# Top_Level.net
KiCad netlist of a schematic drawn in Altium Designer
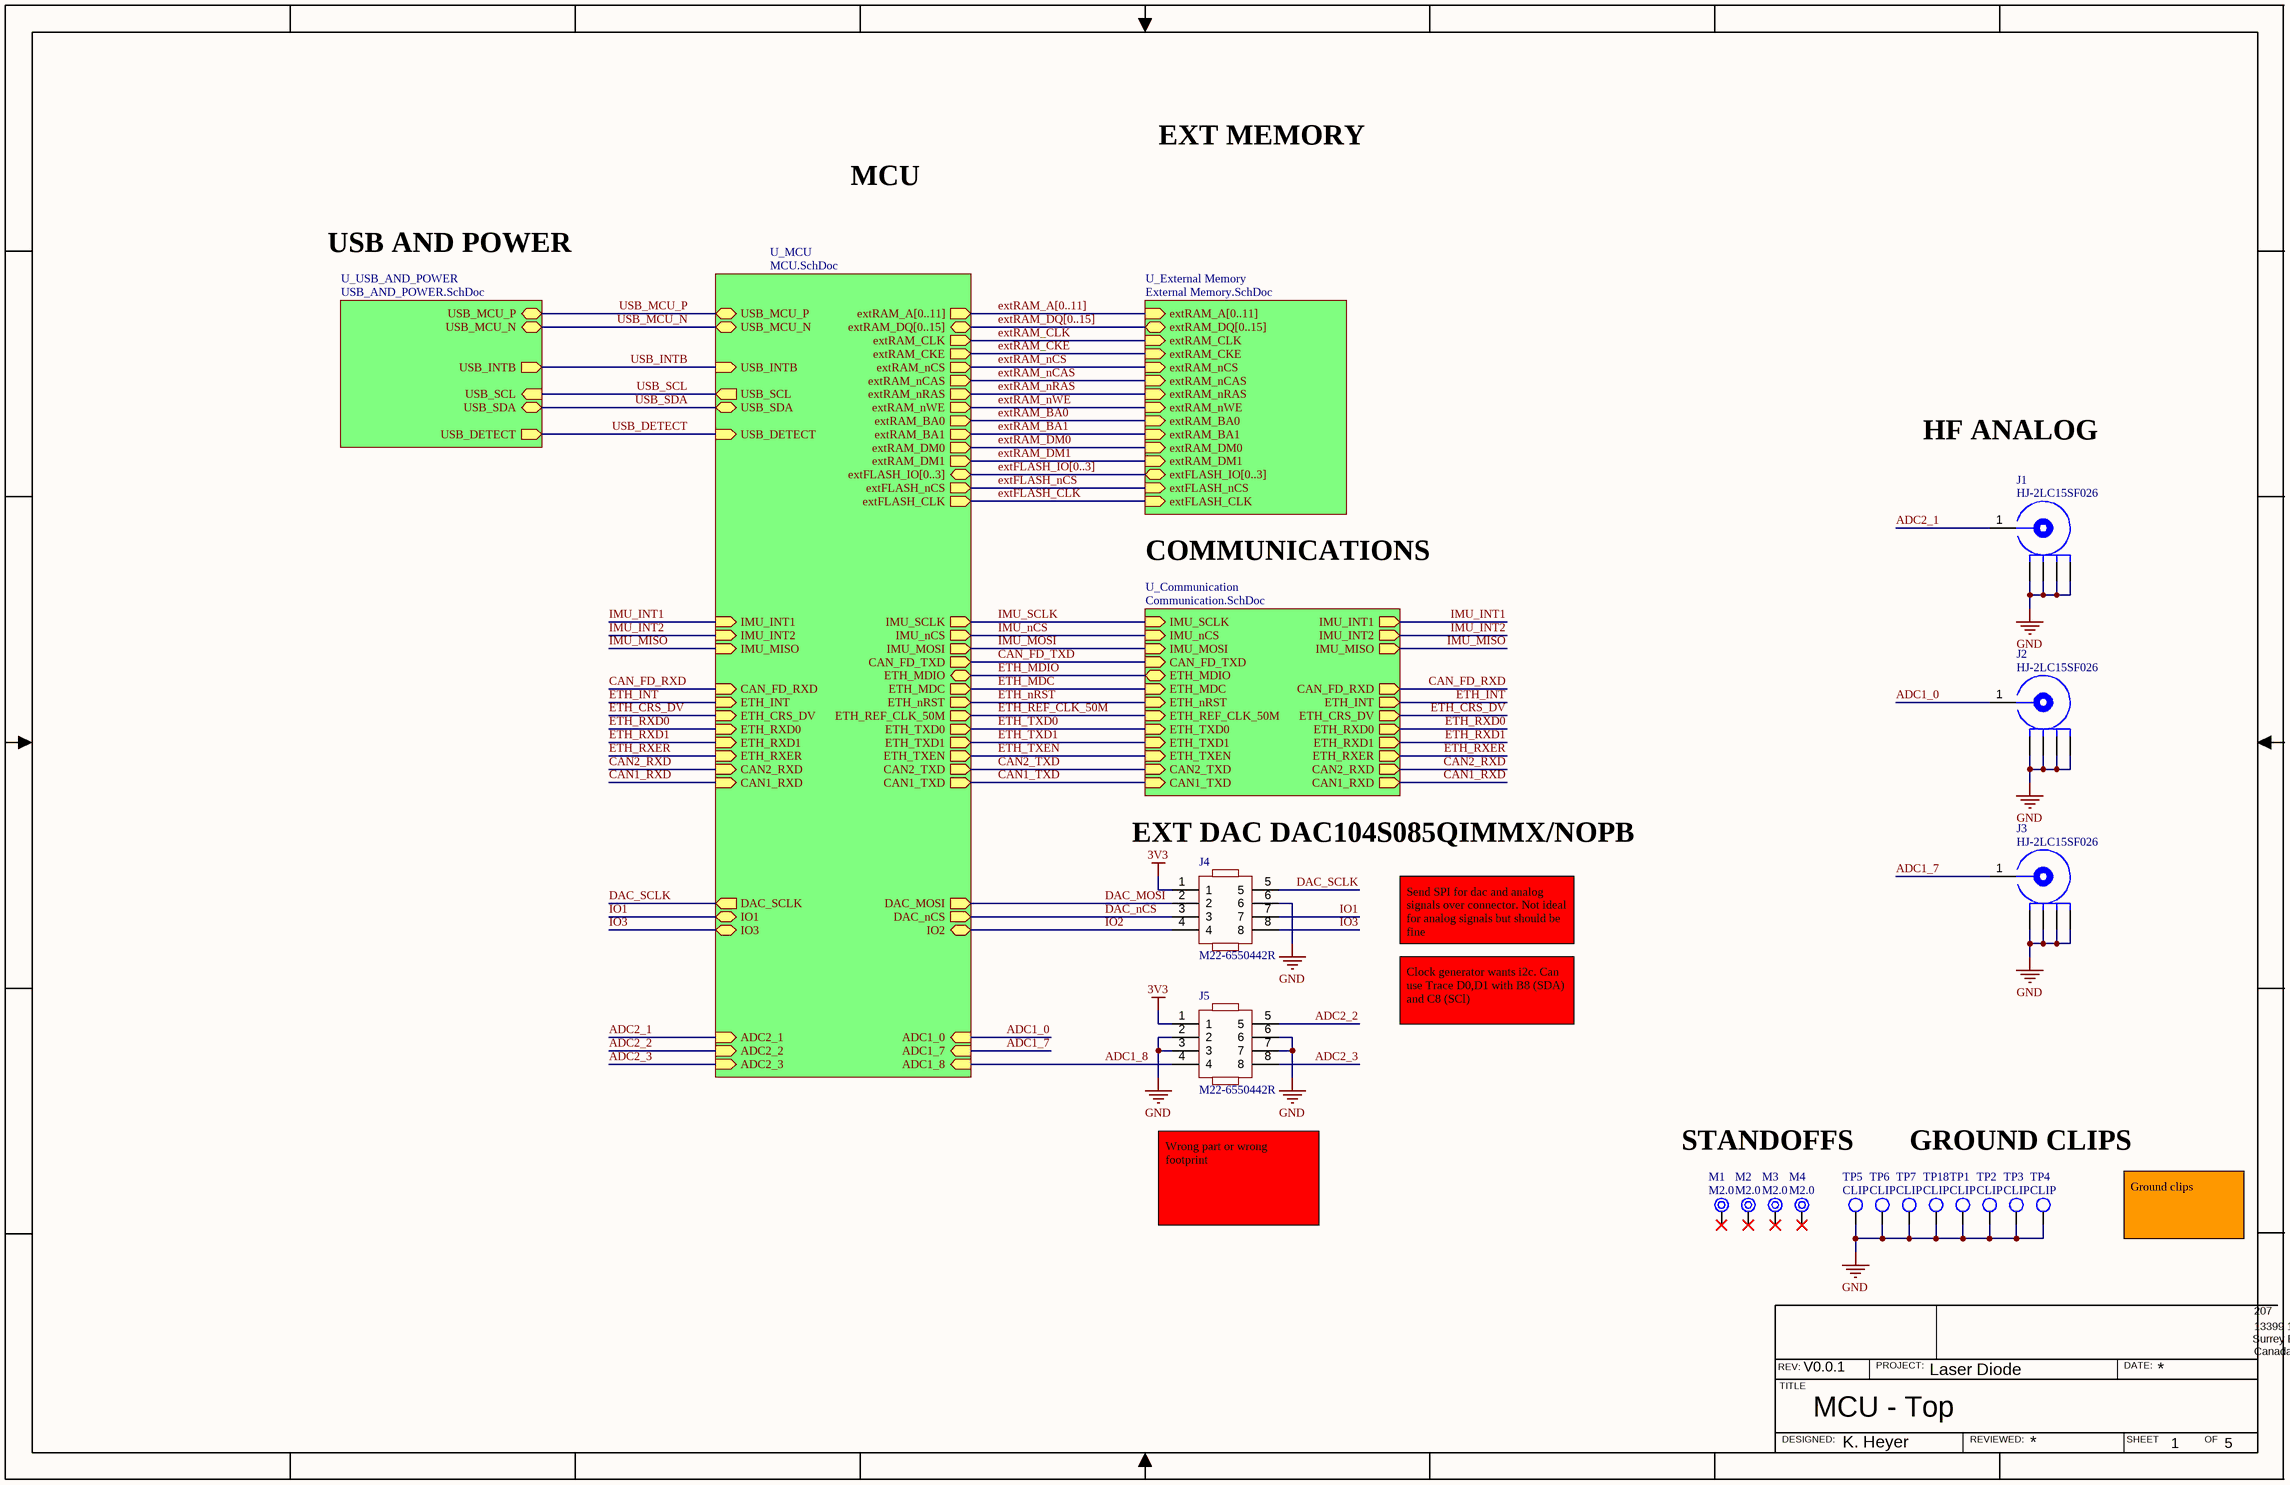
[diagram p0: Top_Level.SchDoc]

(export (version "E")
  (design (tool "Eeschema 10.0.6"))
  (components
    (comp (ref "J1")
      (value "HJ-2LC15SF026")
      (footprint "SMA TH RA BORE")
      (libsource (lib "MCU") (part "CON SMA BORE SMD RA HJ-2LC15SF026"))
    )
    (comp (ref "J2")
      (value "HJ-2LC15SF026")
      (footprint "SMA TH RA BORE")
      (libsource (lib "MCU") (part "CON SMA BORE SMD RA HJ-2LC15SF026"))
    )
    (comp (ref "J3")
      (value "HJ-2LC15SF026")
      (footprint "SMA TH RA BORE")
      (libsource (lib "MCU") (part "CON SMA BORE SMD RA HJ-2LC15SF026"))
    )
    (comp (ref "J4")
      (value "M22-6550442R")
      (footprint "CONN HDR 08 FEMALE RA 2ROW")
      (description "Conn Socket Strip RCP 8 POS 2mm Solder RA SMD T/R")
      (fields (field (name "MANUFACTURER") "Harwin"))
      (libsource (lib "OPAMP_DEV_SOT5_6-23") (part "CONN HDR 08 FEMALE RA 2 ROW"))
    )
    (comp (ref "J5")
      (value "M22-6550442R")
      (footprint "CONN HDR 08 FEMALE RA 2ROW")
      (description "Conn Socket Strip RCP 8 POS 2mm Solder RA SMD T/R")
      (fields (field (name "MANUFACTURER") "Harwin"))
      (libsource (lib "OPAMP_DEV_SOT5_6-23") (part "CONN HDR 08 FEMALE RA 2 ROW"))
    )
    (comp (ref "M1")
      (value "M2.0")
      (footprint "MECH M2.0 UNPLATED")
      (libsource (lib "OPAMP_DEV_SOT5_6-23") (part "MECH M2.0 UNPLATED"))
    )
    (comp (ref "M2")
      (value "M2.0")
      (footprint "MECH M2.0 UNPLATED")
      (libsource (lib "OPAMP_DEV_SOT5_6-23") (part "MECH M2.0 UNPLATED"))
    )
    (comp (ref "M3")
      (value "M2.0")
      (footprint "MECH M2.0 UNPLATED")
      (libsource (lib "OPAMP_DEV_SOT5_6-23") (part "MECH M2.0 UNPLATED"))
    )
    (comp (ref "M4")
      (value "M2.0")
      (footprint "MECH M2.0 UNPLATED")
      (libsource (lib "OPAMP_DEV_SOT5_6-23") (part "MECH M2.0 UNPLATED"))
    )
    (comp (ref "TP1")
      (value "CLIP")
      (footprint "TESTPOINT_CLIP_1206")
      (description "Current Sense Resistors - SMD CHIP CHECKER HT=2.0 1206")
      (fields (field (name "MANUFACTURER") "KOA Speer") (field (name "MANUFACTURER PART NUMBER") "RCWCTE"))
      (libsource (lib "DClassAmp_Symbol") (part "TP CLIP 1206 RCWCTE"))
    )
    (comp (ref "TP2")
      (value "CLIP")
      (footprint "TESTPOINT_CLIP_1206")
      (description "Current Sense Resistors - SMD CHIP CHECKER HT=2.0 1206")
      (fields (field (name "MANUFACTURER") "KOA Speer") (field (name "MANUFACTURER PART NUMBER") "RCWCTE"))
      (libsource (lib "DClassAmp_Symbol") (part "TP CLIP 1206 RCWCTE"))
    )
    (comp (ref "TP3")
      (value "CLIP")
      (footprint "TESTPOINT_CLIP_1206")
      (description "Current Sense Resistors - SMD CHIP CHECKER HT=2.0 1206")
      (fields (field (name "MANUFACTURER") "KOA Speer") (field (name "MANUFACTURER PART NUMBER") "RCWCTE"))
      (libsource (lib "DClassAmp_Symbol") (part "TP CLIP 1206 RCWCTE"))
    )
    (comp (ref "TP4")
      (value "CLIP")
      (footprint "TESTPOINT_CLIP_1206")
      (description "Current Sense Resistors - SMD CHIP CHECKER HT=2.0 1206")
      (fields (field (name "MANUFACTURER") "KOA Speer") (field (name "MANUFACTURER PART NUMBER") "RCWCTE"))
      (libsource (lib "DClassAmp_Symbol") (part "TP CLIP 1206 RCWCTE"))
    )
    (comp (ref "TP5")
      (value "CLIP")
      (footprint "TESTPOINT_CLIP_1206")
      (description "Current Sense Resistors - SMD CHIP CHECKER HT=2.0 1206")
      (fields (field (name "MANUFACTURER") "KOA Speer") (field (name "MANUFACTURER PART NUMBER") "RCWCTE"))
      (libsource (lib "DClassAmp_Symbol") (part "TP CLIP 1206 RCWCTE"))
    )
    (comp (ref "TP6")
      (value "CLIP")
      (footprint "TESTPOINT_CLIP_1206")
      (description "Current Sense Resistors - SMD CHIP CHECKER HT=2.0 1206")
      (fields (field (name "MANUFACTURER") "KOA Speer") (field (name "MANUFACTURER PART NUMBER") "RCWCTE"))
      (libsource (lib "DClassAmp_Symbol") (part "TP CLIP 1206 RCWCTE"))
    )
    (comp (ref "TP7")
      (value "CLIP")
      (footprint "TESTPOINT_CLIP_1206")
      (description "Current Sense Resistors - SMD CHIP CHECKER HT=2.0 1206")
      (fields (field (name "MANUFACTURER") "KOA Speer") (field (name "MANUFACTURER PART NUMBER") "RCWCTE"))
      (libsource (lib "DClassAmp_Symbol") (part "TP CLIP 1206 RCWCTE"))
    )
    (comp (ref "TP18")
      (value "CLIP")
      (footprint "TESTPOINT_CLIP_1206")
      (description "Current Sense Resistors - SMD CHIP CHECKER HT=2.0 1206")
      (fields (field (name "MANUFACTURER") "KOA Speer") (field (name "MANUFACTURER PART NUMBER") "RCWCTE"))
      (libsource (lib "DClassAmp_Symbol") (part "TP CLIP 1206 RCWCTE"))
    )
  )
  (nets
    (net (code "33") (name "/ADC1_0") (class "Default")
      (node (ref "J2") (pin "1") (pinfunction "1_1") (pintype "passive"))
    )
    (net (code "34") (name "/ADC1_7") (class "Default")
      (node (ref "J3") (pin "1") (pinfunction "1_1") (pintype "passive"))
    )
    (net (code "35") (name "/ADC1_8") (class "Default")
      (node (ref "J5") (pin "4") (pinfunction "4_4") (pintype "passive"))
    )
    (net (code "36") (name "/ADC2_1") (class "Default")
      (node (ref "J1") (pin "1") (pinfunction "1_1") (pintype "passive"))
    )
    (net (code "37") (name "/ADC2_2") (class "Default")
      (node (ref "J5") (pin "5") (pinfunction "5_5") (pintype "passive"))
    )
    (net (code "38") (name "/ADC2_3") (class "Default")
      (node (ref "J5") (pin "8") (pinfunction "8_8") (pintype "passive"))
    )
    (net (code "45") (name "/DAC_MOSI") (class "Default")
      (node (ref "J4") (pin "2") (pinfunction "2_2") (pintype "passive"))
    )
    (net (code "46") (name "/DAC_SCLK") (class "Default")
      (node (ref "J4") (pin "5") (pinfunction "5_5") (pintype "passive"))
    )
    (net (code "47") (name "/DAC_nCS") (class "Default")
      (node (ref "J4") (pin "3") (pinfunction "3_3") (pintype "passive"))
    )
    (net (code "66") (name "/IO1") (class "Default")
      (node (ref "J4") (pin "7") (pinfunction "7_7") (pintype "passive"))
    )
    (net (code "67") (name "/IO2") (class "Default")
      (node (ref "J4") (pin "4") (pinfunction "4_4") (pintype "passive"))
    )
    (net (code "68") (name "/IO3") (class "Default")
      (node (ref "J4") (pin "8") (pinfunction "8_8") (pintype "passive"))
    )
    (net (code "90") (name "3V3") (class "Default")
      (node (ref "J4") (pin "1") (pinfunction "1_1") (pintype "passive"))
      (node (ref "J5") (pin "1") (pinfunction "1_1") (pintype "passive"))
    )
    (net (code "91") (name "GND") (class "Default")
      (node (ref "J1") (pin "0") (pinfunction "2_0") (pintype "passive"))
      (node (ref "J2") (pin "0") (pinfunction "2_0") (pintype "passive"))
      (node (ref "J3") (pin "0") (pinfunction "2_0") (pintype "passive"))
      (node (ref "J4") (pin "6") (pinfunction "6_6") (pintype "passive"))
      (node (ref "J5") (pin "2") (pinfunction "2_2") (pintype "passive"))
      (node (ref "J5") (pin "3") (pinfunction "3_3") (pintype "passive"))
      (node (ref "J5") (pin "6") (pinfunction "6_6") (pintype "passive"))
      (node (ref "J5") (pin "7") (pinfunction "7_7") (pintype "passive"))
      (node (ref "TP1") (pin "1") (pinfunction "1_1") (pintype "passive"))
      (node (ref "TP18") (pin "1") (pinfunction "1_1") (pintype "passive"))
      (node (ref "TP2") (pin "1") (pinfunction "1_1") (pintype "passive"))
      (node (ref "TP3") (pin "1") (pinfunction "1_1") (pintype "passive"))
      (node (ref "TP4") (pin "1") (pinfunction "1_1") (pintype "passive"))
      (node (ref "TP5") (pin "1") (pinfunction "1_1") (pintype "passive"))
      (node (ref "TP6") (pin "1") (pinfunction "1_1") (pintype "passive"))
      (node (ref "TP7") (pin "1") (pinfunction "1_1") (pintype "passive"))
    )
    (net (code "92") (name "unconnected-(M1-Pad1)") (class "Default")
      (node (ref "M1") (pin "1") (pinfunction "1_1") (pintype "passive+no_connect"))
    )
    (net (code "93") (name "unconnected-(M2-Pad1)") (class "Default")
      (node (ref "M2") (pin "1") (pinfunction "1_1") (pintype "passive+no_connect"))
    )
    (net (code "94") (name "unconnected-(M3-Pad1)") (class "Default")
      (node (ref "M3") (pin "1") (pinfunction "1_1") (pintype "passive+no_connect"))
    )
    (net (code "95") (name "unconnected-(M4-Pad1)") (class "Default")
      (node (ref "M4") (pin "1") (pinfunction "1_1") (pintype "passive+no_connect"))
    )
  )
)
